# BSB-Board.net
KiCad netlist of a schematic drawn in EAGLE
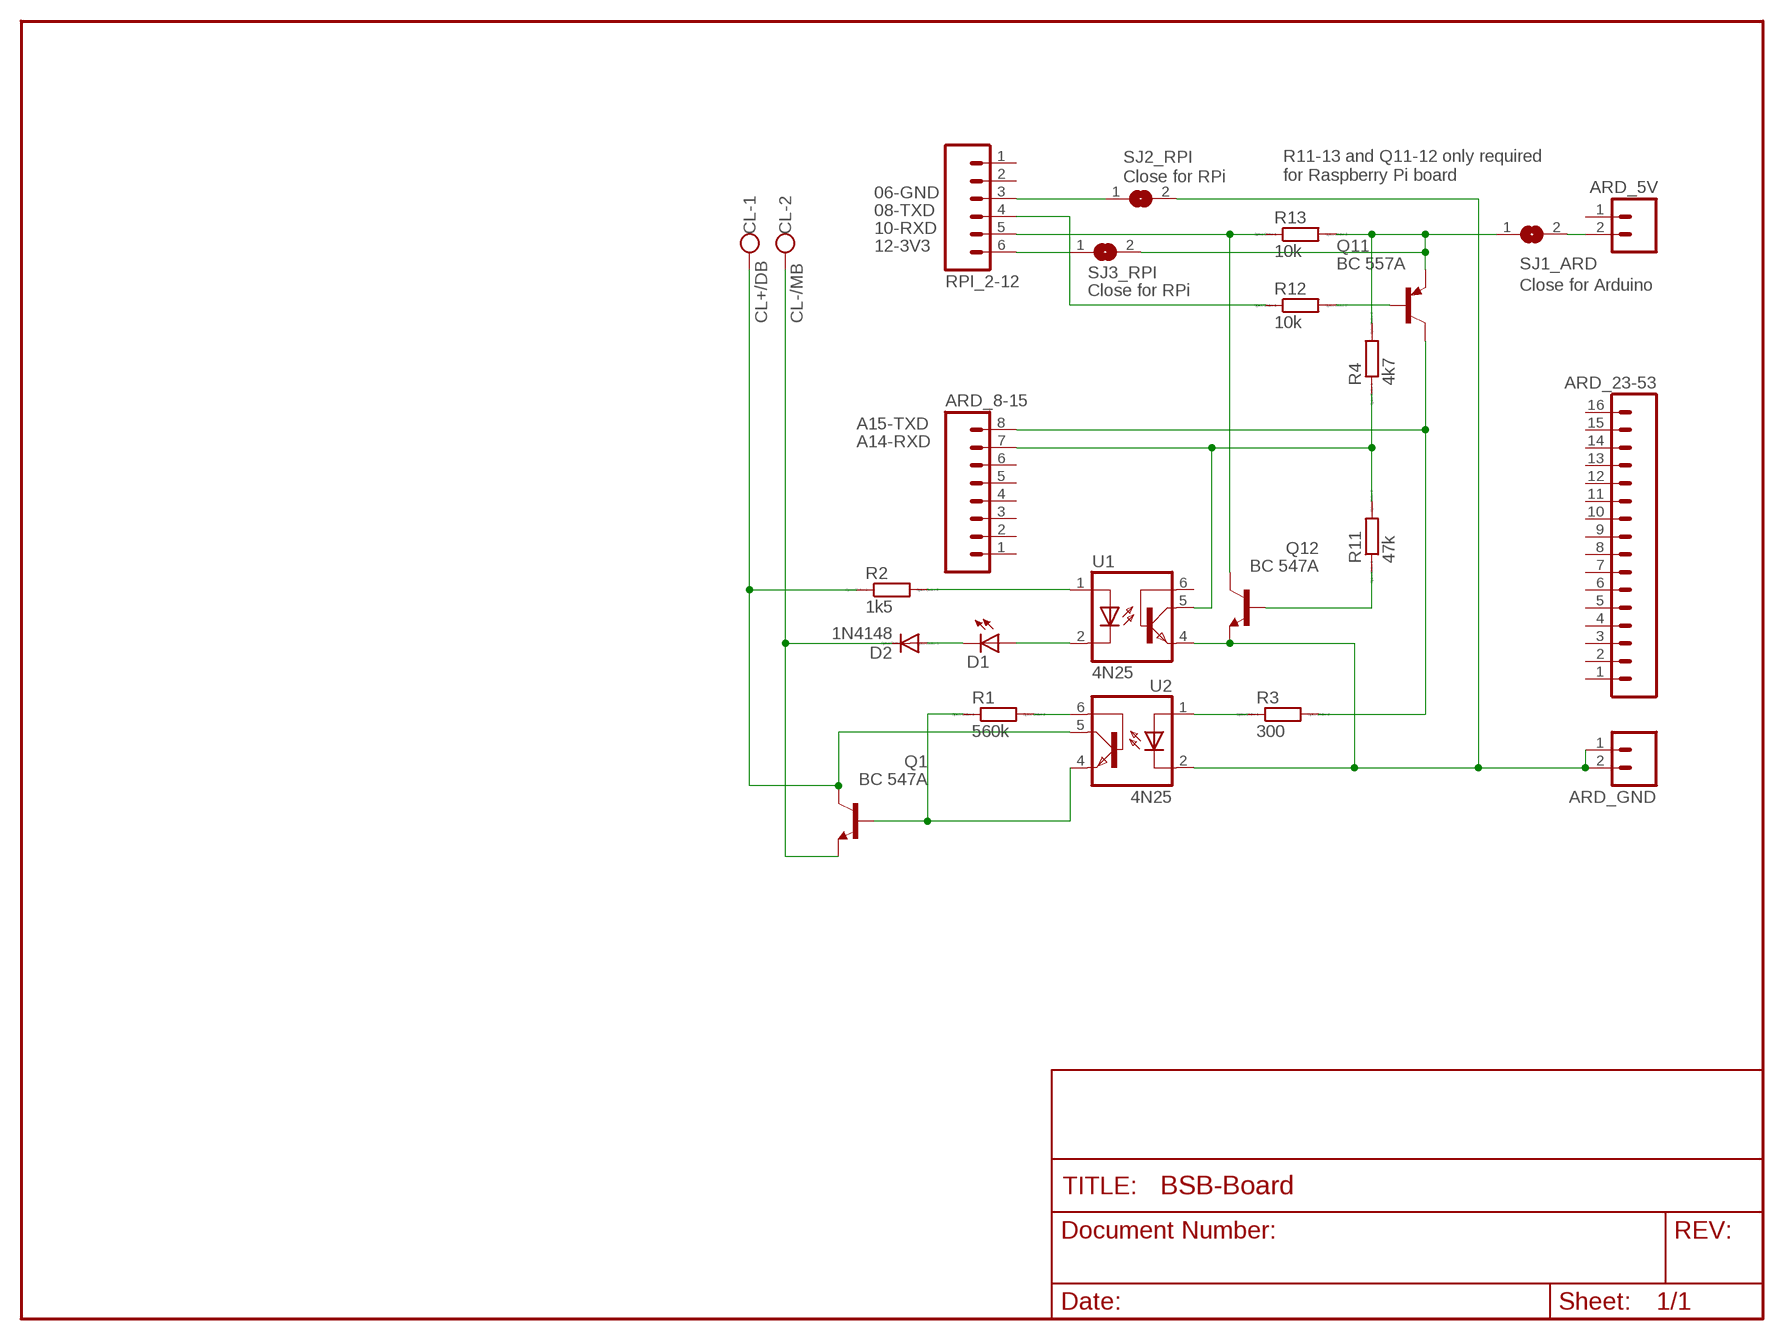
[diagram p0: schematic, sheet 1]

(export (version "E")
  (design (tool "Eeschema 10.0.6"))
  (components
    (comp (ref "ARD_5V")
      (value "M02PTH")
      (footprint "eagle-import:1X02")
      (libsource (lib "eagle-import") (part "M02PTH"))
    )
    (comp (ref "ARD_8-15")
      (value "M08")
      (footprint "eagle-import:1X08_ROUND")
      (libsource (lib "eagle-import") (part "M08"))
    )
    (comp (ref "ARD_23-53")
      (value "M16PTH")
      (footprint "eagle-import:1X16")
      (libsource (lib "eagle-import") (part "M16PTH"))
    )
    (comp (ref "ARD_GND")
      (value "M02PTH")
      (footprint "eagle-import:1X02")
      (libsource (lib "eagle-import") (part "M02PTH"))
    )
    (comp (ref "CL")
      (value "W237-102")
      (footprint "eagle-import:W237-102")
      (fields (field (name "MPN") "237-102"))
      (libsource (lib "eagle-import") (part "W237-102"))
    )
    (comp (ref "D1")
      (value "LEDSQR2X5")
      (footprint "eagle-import:LED2X5")
      (libsource (lib "eagle-import") (part "LEDSQR2X5"))
    )
    (comp (ref "D2")
      (value "1N4148")
      (footprint "eagle-import:DO35-7")
      (libsource (lib "eagle-import") (part "1N4148DO35-7"))
    )
    (comp (ref "Q1")
      (value "BC 547A")
      (footprint "eagle-import:TO92-CBE")
      (libsource (lib "eagle-import") (part "-NPN-TO92-CBEBC547"))
    )
    (comp (ref "Q11")
      (value "BC 557A")
      (footprint "eagle-import:TO92-CBE")
      (libsource (lib "eagle-import") (part "-PNP-TO92-CBE"))
    )
    (comp (ref "Q12")
      (value "BC 547A")
      (footprint "eagle-import:TO92-CBE")
      (libsource (lib "eagle-import") (part "-NPN-TO92-CBEBC547"))
    )
    (comp (ref "R1")
      (value "560k")
      (footprint "eagle-import:0204_7")
      (libsource (lib "eagle-import") (part "R-EU_0204_7"))
    )
    (comp (ref "R2")
      (value "1k5")
      (footprint "eagle-import:0204_7")
      (libsource (lib "eagle-import") (part "R-EU_0204_7"))
    )
    (comp (ref "R3")
      (value "300")
      (footprint "eagle-import:0204_7")
      (libsource (lib "eagle-import") (part "R-EU_0204_7"))
    )
    (comp (ref "R4")
      (value "4k7")
      (footprint "eagle-import:0204_7")
      (libsource (lib "eagle-import") (part "R-EU_0204_7"))
    )
    (comp (ref "R11")
      (value "47k")
      (footprint "eagle-import:0204_7")
      (libsource (lib "eagle-import") (part "R-EU_0204_7"))
    )
    (comp (ref "R12")
      (value "10k")
      (footprint "eagle-import:0204_7")
      (libsource (lib "eagle-import") (part "R-EU_0204_7"))
    )
    (comp (ref "R13")
      (value "10k")
      (footprint "eagle-import:0204_7")
      (libsource (lib "eagle-import") (part "R-EU_0204_7"))
    )
    (comp (ref "RPI_2-12")
      (value "M06SILK_FEMALE_PTH")
      (footprint "eagle-import:1X06")
      (libsource (lib "eagle-import") (part "M06SILK_FEMALE_PTH"))
    )
    (comp (ref "SJ1_ARD")
      (value "Close for Arduino")
      (footprint "eagle-import:SJ")
      (libsource (lib "eagle-import") (part "SJ"))
    )
    (comp (ref "SJ2_RPI")
      (value "Close for RPi")
      (footprint "eagle-import:SJ")
      (libsource (lib "eagle-import") (part "SJ"))
    )
    (comp (ref "SJ3_RPI")
      (value "Close for RPi")
      (footprint "eagle-import:SJ")
      (libsource (lib "eagle-import") (part "SJ"))
    )
    (comp (ref "U1")
      (value "4N25")
      (footprint "eagle-import:DIL06")
      (fields (field (name "MPN") "4N25-M"))
      (libsource (lib "eagle-import") (part "4N?M25"))
    )
    (comp (ref "U2")
      (value "4N25")
      (footprint "eagle-import:DIL06")
      (fields (field (name "MPN") "4N25-M"))
      (libsource (lib "eagle-import") (part "4N?M25"))
    )
  )
  (nets
    (net (code "1") (name "Net-(ARD_5V-Pad2)") (class "Default")
      (node (ref "ARD_5V") (pin "2") (pinfunction "2_2") (pintype "passive"))
      (node (ref "SJ1_ARD") (pin "2") (pinfunction "2_2") (pintype "passive"))
    )
    (net (code "2") (name "Net-(ARD_8-15-Pad8)") (class "Default")
      (node (ref "ARD_8-15") (pin "8") (pinfunction "8_8") (pintype "passive"))
      (node (ref "Q11") (pin "C") (pinfunction "C_C") (pintype "passive"))
      (node (ref "R3") (pin "2") (pinfunction "2_2") (pintype "passive"))
    )
    (net (code "3") (name "Net-(CLA-KL)") (class "Default")
      (node (ref "CL") (pin "1") (pinfunction "KL_1") (pintype "passive"))
      (node (ref "Q1") (pin "C") (pinfunction "C_C") (pintype "passive"))
      (node (ref "R2") (pin "1") (pinfunction "1_1") (pintype "passive"))
      (node (ref "U2") (pin "5") (pinfunction "COL_5") (pintype "passive"))
    )
    (net (code "4") (name "Net-(CLB-KL)") (class "Default")
      (node (ref "CL") (pin "2") (pinfunction "KL_2") (pintype "passive"))
      (node (ref "D2") (pin "C") (pinfunction "C_C") (pintype "passive"))
      (node (ref "Q1") (pin "E") (pinfunction "E_E") (pintype "passive"))
    )
    (net (code "5") (name "Net-(D1-C)") (class "Default")
      (node (ref "D1") (pin "K") (pinfunction "C_K") (pintype "passive"))
      (node (ref "D2") (pin "A") (pinfunction "A_A") (pintype "passive"))
    )
    (net (code "6") (name "Net-(Q11-PadB)") (class "Default")
      (node (ref "Q11") (pin "B") (pinfunction "B_B") (pintype "passive"))
      (node (ref "R12") (pin "2") (pinfunction "2_2") (pintype "passive"))
    )
    (net (code "7") (name "Net-(Q11-PadE)") (class "Default")
      (node (ref "Q11") (pin "E") (pinfunction "E_E") (pintype "passive"))
      (node (ref "R13") (pin "2") (pinfunction "2_2") (pintype "passive"))
      (node (ref "R4") (pin "2") (pinfunction "2_2") (pintype "passive"))
      (node (ref "SJ1_ARD") (pin "1") (pinfunction "1_1") (pintype "passive"))
      (node (ref "SJ3_RPI") (pin "2") (pinfunction "2_2") (pintype "passive"))
    )
    (net (code "8") (name "Net-(Q12-PadB)") (class "Default")
      (node (ref "Q12") (pin "B") (pinfunction "B_B") (pintype "passive"))
      (node (ref "R11") (pin "1") (pinfunction "1_1") (pintype "passive"))
    )
    (net (code "9") (name "Net-(Q12-PadC)") (class "Default")
      (node (ref "Q12") (pin "C") (pinfunction "C_C") (pintype "passive"))
      (node (ref "R13") (pin "1") (pinfunction "1_1") (pintype "passive"))
      (node (ref "RPI_2-12") (pin "5") (pinfunction "5_5") (pintype "passive"))
    )
    (net (code "10") (name "Net-(R12-Pad1)") (class "Default")
      (node (ref "R12") (pin "1") (pinfunction "1_1") (pintype "passive"))
      (node (ref "RPI_2-12") (pin "4") (pinfunction "4_4") (pintype "passive"))
    )
    (net (code "11") (name "Net-(RPI_2-12-Pad3)") (class "Default")
      (node (ref "RPI_2-12") (pin "3") (pinfunction "3_3") (pintype "passive"))
      (node (ref "SJ2_RPI") (pin "1") (pinfunction "1_1") (pintype "passive"))
    )
    (net (code "12") (name "Net-(RPI_2-12-Pad6)") (class "Default")
      (node (ref "RPI_2-12") (pin "6") (pinfunction "6_6") (pintype "passive"))
      (node (ref "SJ3_RPI") (pin "1") (pinfunction "1_1") (pintype "passive"))
    )
    (net (code "13") (name "Net-(U1-A)") (class "Default")
      (node (ref "R2") (pin "2") (pinfunction "2_2") (pintype "passive"))
      (node (ref "U1") (pin "1") (pinfunction "A_1") (pintype "passive"))
    )
    (net (code "14") (name "Net-(U1-C)") (class "Default")
      (node (ref "D1") (pin "A") (pinfunction "A_A") (pintype "passive"))
      (node (ref "U1") (pin "2") (pinfunction "C_2") (pintype "passive"))
    )
    (net (code "15") (name "Net-(U1-COL)") (class "Default")
      (node (ref "ARD_8-15") (pin "7") (pinfunction "7_7") (pintype "passive"))
      (node (ref "R11") (pin "2") (pinfunction "2_2") (pintype "passive"))
      (node (ref "R4") (pin "1") (pinfunction "1_1") (pintype "passive"))
      (node (ref "U1") (pin "5") (pinfunction "COL_5") (pintype "passive"))
    )
    (net (code "16") (name "Net-(U1-EMI)") (class "Default")
      (node (ref "ARD_GND") (pin "1") (pinfunction "1_1") (pintype "passive"))
      (node (ref "ARD_GND") (pin "2") (pinfunction "2_2") (pintype "passive"))
      (node (ref "Q12") (pin "E") (pinfunction "E_E") (pintype "passive"))
      (node (ref "SJ2_RPI") (pin "2") (pinfunction "2_2") (pintype "passive"))
      (node (ref "U1") (pin "4") (pinfunction "EMI_4") (pintype "passive"))
      (node (ref "U2") (pin "2") (pinfunction "C_2") (pintype "passive"))
    )
    (net (code "17") (name "Net-(U2-A)") (class "Default")
      (node (ref "R3") (pin "1") (pinfunction "1_1") (pintype "passive"))
      (node (ref "U2") (pin "1") (pinfunction "A_1") (pintype "passive"))
    )
    (net (code "18") (name "Net-(U2-BAS)") (class "Default")
      (node (ref "R1") (pin "2") (pinfunction "2_2") (pintype "passive"))
      (node (ref "U2") (pin "6") (pinfunction "BAS_6") (pintype "passive"))
    )
    (net (code "19") (name "Net-(U2-EMI)") (class "Default")
      (node (ref "Q1") (pin "B") (pinfunction "B_B") (pintype "passive"))
      (node (ref "R1") (pin "1") (pinfunction "1_1") (pintype "passive"))
      (node (ref "U2") (pin "4") (pinfunction "EMI_4") (pintype "passive"))
    )
    (net (code "20") (name "unconnected-(ARD_5V-Pad1)") (class "Default")
      (node (ref "ARD_5V") (pin "1") (pinfunction "1_1") (pintype "passive"))
    )
    (net (code "21") (name "unconnected-(ARD_8-15-Pad1)") (class "Default")
      (node (ref "ARD_8-15") (pin "1") (pinfunction "1_1") (pintype "passive"))
    )
    (net (code "22") (name "unconnected-(ARD_8-15-Pad2)") (class "Default")
      (node (ref "ARD_8-15") (pin "2") (pinfunction "2_2") (pintype "passive"))
    )
    (net (code "23") (name "unconnected-(ARD_8-15-Pad3)") (class "Default")
      (node (ref "ARD_8-15") (pin "3") (pinfunction "3_3") (pintype "passive"))
    )
    (net (code "24") (name "unconnected-(ARD_8-15-Pad4)") (class "Default")
      (node (ref "ARD_8-15") (pin "4") (pinfunction "4_4") (pintype "passive"))
    )
    (net (code "25") (name "unconnected-(ARD_8-15-Pad5)") (class "Default")
      (node (ref "ARD_8-15") (pin "5") (pinfunction "5_5") (pintype "passive"))
    )
    (net (code "26") (name "unconnected-(ARD_8-15-Pad6)") (class "Default")
      (node (ref "ARD_8-15") (pin "6") (pinfunction "6_6") (pintype "passive"))
    )
    (net (code "27") (name "unconnected-(ARD_23-53-Pad1)") (class "Default")
      (node (ref "ARD_23-53") (pin "1") (pinfunction "1_1") (pintype "passive"))
    )
    (net (code "28") (name "unconnected-(ARD_23-53-Pad2)") (class "Default")
      (node (ref "ARD_23-53") (pin "2") (pinfunction "2_2") (pintype "passive"))
    )
    (net (code "29") (name "unconnected-(ARD_23-53-Pad3)") (class "Default")
      (node (ref "ARD_23-53") (pin "3") (pinfunction "3_3") (pintype "passive"))
    )
    (net (code "30") (name "unconnected-(ARD_23-53-Pad4)") (class "Default")
      (node (ref "ARD_23-53") (pin "4") (pinfunction "4_4") (pintype "passive"))
    )
    (net (code "31") (name "unconnected-(ARD_23-53-Pad5)") (class "Default")
      (node (ref "ARD_23-53") (pin "5") (pinfunction "5_5") (pintype "passive"))
    )
    (net (code "32") (name "unconnected-(ARD_23-53-Pad6)") (class "Default")
      (node (ref "ARD_23-53") (pin "6") (pinfunction "6_6") (pintype "passive"))
    )
    (net (code "33") (name "unconnected-(ARD_23-53-Pad7)") (class "Default")
      (node (ref "ARD_23-53") (pin "7") (pinfunction "7_7") (pintype "passive"))
    )
    (net (code "34") (name "unconnected-(ARD_23-53-Pad8)") (class "Default")
      (node (ref "ARD_23-53") (pin "8") (pinfunction "8_8") (pintype "passive"))
    )
    (net (code "35") (name "unconnected-(ARD_23-53-Pad9)") (class "Default")
      (node (ref "ARD_23-53") (pin "9") (pinfunction "9_9") (pintype "passive"))
    )
    (net (code "36") (name "unconnected-(ARD_23-53-Pad10)") (class "Default")
      (node (ref "ARD_23-53") (pin "10") (pinfunction "10_10") (pintype "passive"))
    )
    (net (code "37") (name "unconnected-(ARD_23-53-Pad11)") (class "Default")
      (node (ref "ARD_23-53") (pin "11") (pinfunction "11_11") (pintype "passive"))
    )
    (net (code "38") (name "unconnected-(ARD_23-53-Pad12)") (class "Default")
      (node (ref "ARD_23-53") (pin "12") (pinfunction "12_12") (pintype "passive"))
    )
    (net (code "39") (name "unconnected-(ARD_23-53-Pad13)") (class "Default")
      (node (ref "ARD_23-53") (pin "13") (pinfunction "13_13") (pintype "passive"))
    )
    (net (code "40") (name "unconnected-(ARD_23-53-Pad14)") (class "Default")
      (node (ref "ARD_23-53") (pin "14") (pinfunction "14_14") (pintype "passive"))
    )
    (net (code "41") (name "unconnected-(ARD_23-53-Pad15)") (class "Default")
      (node (ref "ARD_23-53") (pin "15") (pinfunction "15_15") (pintype "passive"))
    )
    (net (code "42") (name "unconnected-(ARD_23-53-Pad16)") (class "Default")
      (node (ref "ARD_23-53") (pin "16") (pinfunction "16_16") (pintype "passive"))
    )
    (net (code "43") (name "unconnected-(RPI_2-12-Pad1)") (class "Default")
      (node (ref "RPI_2-12") (pin "1") (pinfunction "1_1") (pintype "passive"))
    )
    (net (code "44") (name "unconnected-(RPI_2-12-Pad2)") (class "Default")
      (node (ref "RPI_2-12") (pin "2") (pinfunction "2_2") (pintype "passive"))
    )
    (net (code "45") (name "unconnected-(U1-BAS-Pad6)") (class "Default")
      (node (ref "U1") (pin "6") (pinfunction "BAS_6") (pintype "passive"))
    )
  )
)
